# nixie_tester.net
KiCad netlist of a schematic drawn in EAGLE
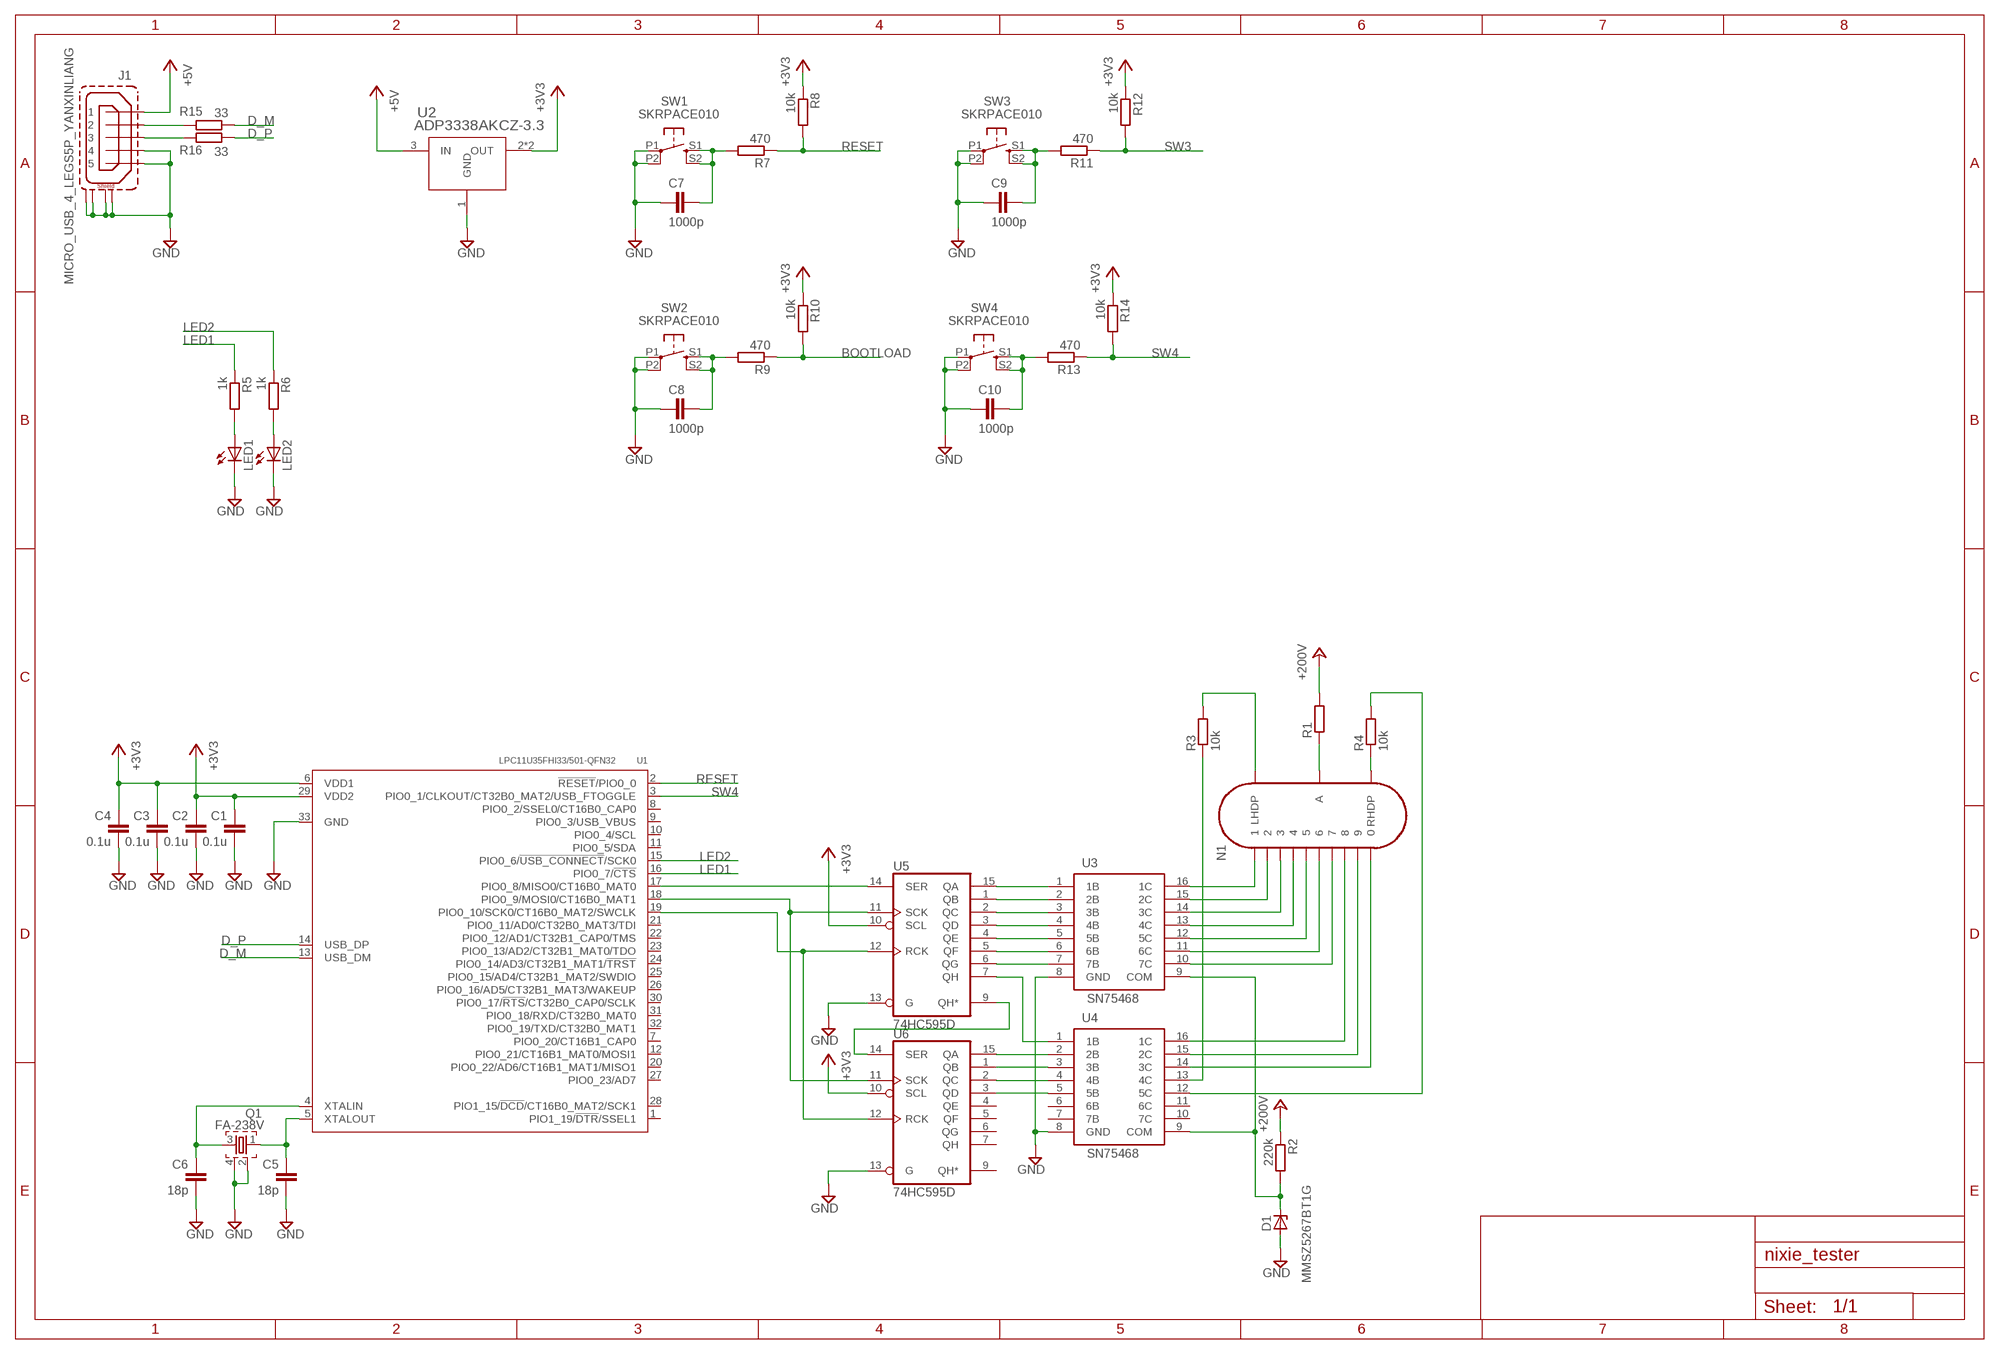
[diagram p0: schematic, sheet 1]

(export (version "E")
  (design (tool "Eeschema 10.0.6"))
  (components
    (comp (ref "C1")
      (value "0.1u")
      (footprint "eagle-import:C0603")
      (libsource (lib "eagle-import") (part "C-EUC0603"))
    )
    (comp (ref "C2")
      (value "0.1u")
      (footprint "eagle-import:C0603")
      (libsource (lib "eagle-import") (part "C-EUC0603"))
    )
    (comp (ref "C3")
      (value "0.1u")
      (footprint "eagle-import:C0603")
      (libsource (lib "eagle-import") (part "C-EUC0603"))
    )
    (comp (ref "C4")
      (value "0.1u")
      (footprint "eagle-import:C0603")
      (libsource (lib "eagle-import") (part "C-EUC0603"))
    )
    (comp (ref "C5")
      (value "18p")
      (footprint "eagle-import:C0603")
      (libsource (lib "eagle-import") (part "C-EUC0603"))
    )
    (comp (ref "C6")
      (value "18p")
      (footprint "eagle-import:C0603")
      (libsource (lib "eagle-import") (part "C-EUC0603"))
    )
    (comp (ref "C7")
      (value "1000p")
      (footprint "eagle-import:C0603")
      (libsource (lib "eagle-import") (part "C-EUC0603"))
    )
    (comp (ref "C8")
      (value "1000p")
      (footprint "eagle-import:C0603")
      (libsource (lib "eagle-import") (part "C-EUC0603"))
    )
    (comp (ref "C9")
      (value "1000p")
      (footprint "eagle-import:C0603")
      (libsource (lib "eagle-import") (part "C-EUC0603"))
    )
    (comp (ref "C10")
      (value "1000p")
      (footprint "eagle-import:C0603")
      (libsource (lib "eagle-import") (part "C-EUC0603"))
    )
    (comp (ref "D1")
      (value "MMSZ5267BT1G")
      (footprint "eagle-import:SOD123")
      (libsource (lib "eagle-import") (part "MMSZ5267BT1G"))
    )
    (comp (ref "J1")
      (value "MICRO_USB_4_LEGS5P_YANXINLIANG")
      (footprint "eagle-import:MICRO_USB_4_LEGS5P_YANXINLIANG")
      (libsource (lib "eagle-import") (part "MICRO_USB_4_LEGS5P_YANXINLIANG"))
    )
    (comp (ref "LED1")
      (value "LEDCHIPLED_0603")
      (footprint "eagle-import:CHIPLED_0603")
      (libsource (lib "eagle-import") (part "LEDCHIPLED_0603"))
    )
    (comp (ref "LED2")
      (value "LEDCHIPLED_0603")
      (footprint "eagle-import:CHIPLED_0603")
      (libsource (lib "eagle-import") (part "LEDCHIPLED_0603"))
    )
    (comp (ref "N1")
      (value "IN-14")
      (footprint "eagle-import:IN-14")
      (libsource (lib "eagle-import") (part "IN-14"))
    )
    (comp (ref "Q1")
      (value "FA-238V")
      (footprint "eagle-import:FA238-V")
      (libsource (lib "eagle-import") (part "FA-238V"))
    )
    (comp (ref "R1")
      (value "R-EU_R1206")
      (footprint "eagle-import:R1206")
      (libsource (lib "eagle-import") (part "R-EU_R1206"))
    )
    (comp (ref "R2")
      (value "220k")
      (footprint "eagle-import:R0603")
      (libsource (lib "eagle-import") (part "R-EU_R0603"))
    )
    (comp (ref "R3")
      (value "10k")
      (footprint "eagle-import:R0603")
      (libsource (lib "eagle-import") (part "R-EU_R0603"))
    )
    (comp (ref "R4")
      (value "10k")
      (footprint "eagle-import:R0603")
      (libsource (lib "eagle-import") (part "R-EU_R0603"))
    )
    (comp (ref "R5")
      (value "1k")
      (footprint "eagle-import:R0603")
      (libsource (lib "eagle-import") (part "R-EU_R0603"))
    )
    (comp (ref "R6")
      (value "1k")
      (footprint "eagle-import:R0603")
      (libsource (lib "eagle-import") (part "R-EU_R0603"))
    )
    (comp (ref "R7")
      (value "470")
      (footprint "eagle-import:R0603")
      (libsource (lib "eagle-import") (part "R-EU_R0603"))
    )
    (comp (ref "R8")
      (value "10k")
      (footprint "eagle-import:R0603")
      (libsource (lib "eagle-import") (part "R-EU_R0603"))
    )
    (comp (ref "R9")
      (value "470")
      (footprint "eagle-import:R0603")
      (libsource (lib "eagle-import") (part "R-EU_R0603"))
    )
    (comp (ref "R10")
      (value "10k")
      (footprint "eagle-import:R0603")
      (libsource (lib "eagle-import") (part "R-EU_R0603"))
    )
    (comp (ref "R11")
      (value "470")
      (footprint "eagle-import:R0603")
      (libsource (lib "eagle-import") (part "R-EU_R0603"))
    )
    (comp (ref "R12")
      (value "10k")
      (footprint "eagle-import:R0603")
      (libsource (lib "eagle-import") (part "R-EU_R0603"))
    )
    (comp (ref "R13")
      (value "470")
      (footprint "eagle-import:R0603")
      (libsource (lib "eagle-import") (part "R-EU_R0603"))
    )
    (comp (ref "R14")
      (value "10k")
      (footprint "eagle-import:R0603")
      (libsource (lib "eagle-import") (part "R-EU_R0603"))
    )
    (comp (ref "R15")
      (value "33")
      (footprint "eagle-import:R0603")
      (libsource (lib "eagle-import") (part "R-EU_R0603"))
    )
    (comp (ref "R16")
      (value "33")
      (footprint "eagle-import:R0603")
      (libsource (lib "eagle-import") (part "R-EU_R0603"))
    )
    (comp (ref "SW1")
      (value "SKRPACE010")
      (footprint "eagle-import:SKRPACE010")
      (libsource (lib "eagle-import") (part "SKRPACE010"))
    )
    (comp (ref "SW2")
      (value "SKRPACE010")
      (footprint "eagle-import:SKRPACE010")
      (libsource (lib "eagle-import") (part "SKRPACE010"))
    )
    (comp (ref "SW3")
      (value "SKRPACE010")
      (footprint "eagle-import:SKRPACE010")
      (libsource (lib "eagle-import") (part "SKRPACE010"))
    )
    (comp (ref "SW4")
      (value "SKRPACE010")
      (footprint "eagle-import:SKRPACE010")
      (libsource (lib "eagle-import") (part "SKRPACE010"))
    )
    (comp (ref "U1")
      (value "LPC11U35FHI33/501-QFN32")
      (footprint "eagle-import:QFN32G-0.5-5X5MM")
      (fields (field (name "MPN") "LPC11U35FHI33/501"))
      (libsource (lib "eagle-import") (part "MCU-LPC11U35FHI33/501(QFN32)"))
    )
    (comp (ref "U2")
      (value "ADP3338AKCZ-3.3")
      (footprint "eagle-import:SOT233")
      (libsource (lib "eagle-import") (part "ADP3338AKCZ-3.3"))
    )
    (comp (ref "U3")
      (value "SN75468")
      (footprint "eagle-import:R-PDSO-G16")
      (libsource (lib "eagle-import") (part "SN75468"))
    )
    (comp (ref "U4")
      (value "SN75468")
      (footprint "eagle-import:R-PDSO-G16")
      (libsource (lib "eagle-import") (part "SN75468"))
    )
    (comp (ref "U5")
      (value "74HC595D")
      (footprint "eagle-import:SO16")
      (libsource (lib "eagle-import") (part "74595DHC"))
    )
    (comp (ref "U6")
      (value "74HC595D")
      (footprint "eagle-import:SO16")
      (libsource (lib "eagle-import") (part "74595DHC"))
    )
  )
  (nets
    (net (code "1") (name "+3V3") (class "Default")
      (node (ref "C1") (pin "1") (pinfunction "1_1") (pintype "passive"))
      (node (ref "C2") (pin "1") (pinfunction "1_1") (pintype "passive"))
      (node (ref "C3") (pin "1") (pinfunction "1_1") (pintype "passive"))
      (node (ref "C4") (pin "1") (pinfunction "1_1") (pintype "passive"))
      (node (ref "R10") (pin "1") (pinfunction "1_1") (pintype "passive"))
      (node (ref "R12") (pin "1") (pinfunction "1_1") (pintype "passive"))
      (node (ref "R14") (pin "1") (pinfunction "1_1") (pintype "passive"))
      (node (ref "R8") (pin "1") (pinfunction "1_1") (pintype "passive"))
      (node (ref "U1") (pin "29") (pinfunction "VDD2_29") (pintype "bidirectional"))
      (node (ref "U1") (pin "6") (pinfunction "VDD1_6") (pintype "bidirectional"))
      (node (ref "U2") (pin "2") (pinfunction "OUT_2") (pintype "passive"))
      (node (ref "U2") (pin "4") (pinfunction "OUT_4") (pintype "passive"))
      (node (ref "U5") (pin "10") (pinfunction "SCL_10") (pintype "input"))
      (node (ref "U6") (pin "10") (pinfunction "SCL_10") (pintype "input"))
    )
    (net (code "2") (name "+5V") (class "Default")
      (node (ref "J1") (pin "1") (pinfunction "1_1") (pintype "input"))
      (node (ref "U2") (pin "3") (pinfunction "IN_3") (pintype "passive"))
    )
    (net (code "3") (name "+200V") (class "Default")
      (node (ref "R1") (pin "2") (pinfunction "2_2") (pintype "passive"))
      (node (ref "R2") (pin "1") (pinfunction "1_1") (pintype "passive"))
    )
    (net (code "4") (name "/BOOTLOAD") (class "Default")
      (node (ref "R10") (pin "2") (pinfunction "2_2") (pintype "passive"))
      (node (ref "R9") (pin "1") (pinfunction "1_1") (pintype "passive"))
    )
    (net (code "5") (name "/D_M") (class "Default")
      (node (ref "R15") (pin "1") (pinfunction "1_1") (pintype "passive"))
      (node (ref "U1") (pin "13") (pinfunction "USB_DM_13") (pintype "bidirectional"))
    )
    (net (code "6") (name "/D_P") (class "Default")
      (node (ref "R16") (pin "1") (pinfunction "1_1") (pintype "passive"))
      (node (ref "U1") (pin "14") (pinfunction "USB_DP_14") (pintype "bidirectional"))
    )
    (net (code "7") (name "/LED1") (class "Default")
      (node (ref "R5") (pin "1") (pinfunction "1_1") (pintype "passive"))
      (node (ref "U1") (pin "16") (pinfunction "PIO0_7/~{CTS}_16") (pintype "bidirectional"))
    )
    (net (code "8") (name "/LED2") (class "Default")
      (node (ref "R6") (pin "1") (pinfunction "1_1") (pintype "passive"))
      (node (ref "U1") (pin "15") (pinfunction "PIO0_6/~{USB_CONNECT}/SCK0_15") (pintype "bidirectional"))
    )
    (net (code "9") (name "/RESET") (class "Default")
      (node (ref "R7") (pin "1") (pinfunction "1_1") (pintype "passive"))
      (node (ref "R8") (pin "2") (pinfunction "2_2") (pintype "passive"))
      (node (ref "U1") (pin "2") (pinfunction "~{RESET}/PIO0_0_2") (pintype "bidirectional"))
    )
    (net (code "10") (name "/SW3") (class "Default")
      (node (ref "R11") (pin "1") (pinfunction "1_1") (pintype "passive"))
      (node (ref "R12") (pin "2") (pinfunction "2_2") (pintype "passive"))
    )
    (net (code "11") (name "/SW4") (class "Default")
      (node (ref "R13") (pin "1") (pinfunction "1_1") (pintype "passive"))
      (node (ref "R14") (pin "2") (pinfunction "2_2") (pintype "passive"))
      (node (ref "U1") (pin "3") (pinfunction "PIO0_1/CLKOUT/CT32B0_MAT2/USB_FTOGGLE_3") (pintype "bidirectional"))
    )
    (net (code "12") (name "GND") (class "Default")
      (node (ref "C1") (pin "2") (pinfunction "2_2") (pintype "passive"))
      (node (ref "C10") (pin "1") (pinfunction "1_1") (pintype "passive"))
      (node (ref "C2") (pin "2") (pinfunction "2_2") (pintype "passive"))
      (node (ref "C3") (pin "2") (pinfunction "2_2") (pintype "passive"))
      (node (ref "C4") (pin "2") (pinfunction "2_2") (pintype "passive"))
      (node (ref "C5") (pin "2") (pinfunction "2_2") (pintype "passive"))
      (node (ref "C6") (pin "2") (pinfunction "2_2") (pintype "passive"))
      (node (ref "C7") (pin "1") (pinfunction "1_1") (pintype "passive"))
      (node (ref "C8") (pin "1") (pinfunction "1_1") (pintype "passive"))
      (node (ref "C9") (pin "1") (pinfunction "1_1") (pintype "passive"))
      (node (ref "D1") (pin "A") (pinfunction "A_A") (pintype "passive"))
      (node (ref "J1") (pin "4") (pinfunction "4_4") (pintype "input"))
      (node (ref "J1") (pin "5") (pinfunction "5_5") (pintype "input"))
      (node (ref "J1") (pin "S3") (pinfunction "S3_S3") (pintype "passive"))
      (node (ref "J1") (pin "S4") (pinfunction "S4_S4") (pintype "passive"))
      (node (ref "J1") (pin "S5") (pinfunction "S5_S5") (pintype "passive"))
      (node (ref "J1") (pin "S6") (pinfunction "S6_S6") (pintype "passive"))
      (node (ref "LED1") (pin "C") (pinfunction "C_C") (pintype "passive"))
      (node (ref "LED2") (pin "C") (pinfunction "C_C") (pintype "passive"))
      (node (ref "Q1") (pin "2") (pinfunction "2_2") (pintype "passive"))
      (node (ref "Q1") (pin "4") (pinfunction "4_4") (pintype "passive"))
      (node (ref "SW1") (pin "P1") (pinfunction "P_P1") (pintype "passive"))
      (node (ref "SW1") (pin "P2") (pinfunction "P1_P2") (pintype "passive"))
      (node (ref "SW2") (pin "P1") (pinfunction "P_P1") (pintype "passive"))
      (node (ref "SW2") (pin "P2") (pinfunction "P1_P2") (pintype "passive"))
      (node (ref "SW3") (pin "P1") (pinfunction "P_P1") (pintype "passive"))
      (node (ref "SW3") (pin "P2") (pinfunction "P1_P2") (pintype "passive"))
      (node (ref "SW4") (pin "P1") (pinfunction "P_P1") (pintype "passive"))
      (node (ref "SW4") (pin "P2") (pinfunction "P1_P2") (pintype "passive"))
      (node (ref "U1") (pin "33") (pinfunction "GND_33") (pintype "bidirectional"))
      (node (ref "U2") (pin "1") (pinfunction "GND_1") (pintype "passive"))
      (node (ref "U3") (pin "8") (pinfunction "GND_8") (pintype "bidirectional"))
      (node (ref "U4") (pin "8") (pinfunction "GND_8") (pintype "bidirectional"))
      (node (ref "U5") (pin "13") (pinfunction "G_13") (pintype "input"))
      (node (ref "U6") (pin "13") (pinfunction "G_13") (pintype "input"))
    )
    (net (code "13") (name "Net-(D1-C)") (class "Default")
      (node (ref "D1") (pin "K") (pinfunction "C_K") (pintype "passive"))
      (node (ref "R2") (pin "2") (pinfunction "2_2") (pintype "passive"))
      (node (ref "U3") (pin "9") (pinfunction "COM_9") (pintype "bidirectional"))
      (node (ref "U4") (pin "9") (pinfunction "COM_9") (pintype "bidirectional"))
    )
    (net (code "14") (name "Net-(J1-Pad2)") (class "Default")
      (node (ref "J1") (pin "2") (pinfunction "2_2") (pintype "input"))
      (node (ref "R15") (pin "2") (pinfunction "2_2") (pintype "passive"))
    )
    (net (code "15") (name "Net-(J1-Pad3)") (class "Default")
      (node (ref "J1") (pin "3") (pinfunction "3_3") (pintype "input"))
      (node (ref "R16") (pin "2") (pinfunction "2_2") (pintype "passive"))
    )
    (net (code "16") (name "Net-(LED1-PadA)") (class "Default")
      (node (ref "LED1") (pin "A") (pinfunction "A_A") (pintype "passive"))
      (node (ref "R5") (pin "2") (pinfunction "2_2") (pintype "passive"))
    )
    (net (code "17") (name "Net-(LED2-PadA)") (class "Default")
      (node (ref "LED2") (pin "A") (pinfunction "A_A") (pintype "passive"))
      (node (ref "R6") (pin "2") (pinfunction "2_2") (pintype "passive"))
    )
    (net (code "18") (name "Net-(N1-PadA)") (class "Default")
      (node (ref "N1") (pin "A") (pinfunction "A_A") (pintype "bidirectional"))
      (node (ref "R1") (pin "1") (pinfunction "1_1") (pintype "passive"))
    )
    (net (code "19") (name "Net-(N1-PadLHDP)") (class "Default")
      (node (ref "N1") (pin "LHDP") (pinfunction "LHDP_LHDP") (pintype "bidirectional"))
      (node (ref "R3") (pin "2") (pinfunction "2_2") (pintype "passive"))
    )
    (net (code "20") (name "Net-(N1-PadRHDP)") (class "Default")
      (node (ref "N1") (pin "RHDP") (pinfunction "RHDP_RHDP") (pintype "bidirectional"))
      (node (ref "R4") (pin "1") (pinfunction "1_1") (pintype "passive"))
    )
    (net (code "21") (name "Net-(SW1-S)") (class "Default")
      (node (ref "C7") (pin "2") (pinfunction "2_2") (pintype "passive"))
      (node (ref "R7") (pin "2") (pinfunction "2_2") (pintype "passive"))
      (node (ref "SW1") (pin "S1") (pinfunction "S_S1") (pintype "passive"))
      (node (ref "SW1") (pin "S2") (pinfunction "S1_S2") (pintype "passive"))
    )
    (net (code "22") (name "Net-(SW2-S)") (class "Default")
      (node (ref "C8") (pin "2") (pinfunction "2_2") (pintype "passive"))
      (node (ref "R9") (pin "2") (pinfunction "2_2") (pintype "passive"))
      (node (ref "SW2") (pin "S1") (pinfunction "S_S1") (pintype "passive"))
      (node (ref "SW2") (pin "S2") (pinfunction "S1_S2") (pintype "passive"))
    )
    (net (code "23") (name "Net-(SW3-S)") (class "Default")
      (node (ref "C9") (pin "2") (pinfunction "2_2") (pintype "passive"))
      (node (ref "R11") (pin "2") (pinfunction "2_2") (pintype "passive"))
      (node (ref "SW3") (pin "S1") (pinfunction "S_S1") (pintype "passive"))
      (node (ref "SW3") (pin "S2") (pinfunction "S1_S2") (pintype "passive"))
    )
    (net (code "24") (name "Net-(SW4-S)") (class "Default")
      (node (ref "C10") (pin "2") (pinfunction "2_2") (pintype "passive"))
      (node (ref "R13") (pin "2") (pinfunction "2_2") (pintype "passive"))
      (node (ref "SW4") (pin "S1") (pinfunction "S_S1") (pintype "passive"))
      (node (ref "SW4") (pin "S2") (pinfunction "S1_S2") (pintype "passive"))
    )
    (net (code "25") (name "Net-(U1-PIO0_8{slash}MISO0{slash}CT16B0_MAT0)") (class "Default")
      (node (ref "U1") (pin "17") (pinfunction "PIO0_8/MISO0/CT16B0_MAT0_17") (pintype "bidirectional"))
      (node (ref "U5") (pin "14") (pinfunction "SER_14") (pintype "input"))
    )
    (net (code "26") (name "Net-(U1-PIO0_9{slash}MOSI0{slash}CT16B0_MAT1)") (class "Default")
      (node (ref "U1") (pin "18") (pinfunction "PIO0_9/MOSI0/CT16B0_MAT1_18") (pintype "bidirectional"))
      (node (ref "U5") (pin "11") (pinfunction "SCK_11") (pintype "input"))
      (node (ref "U6") (pin "11") (pinfunction "SCK_11") (pintype "input"))
    )
    (net (code "27") (name "Net-(U1-PIO0_10{slash}SCK0{slash}CT16B0_MAT2{slash}SWCLK)") (class "Default")
      (node (ref "U1") (pin "19") (pinfunction "PIO0_10/SCK0/CT16B0_MAT2/SWCLK_19") (pintype "bidirectional"))
      (node (ref "U5") (pin "12") (pinfunction "RCK_12") (pintype "input"))
      (node (ref "U6") (pin "12") (pinfunction "RCK_12") (pintype "input"))
    )
    (net (code "28") (name "Net-(U1-XTALIN)") (class "Default")
      (node (ref "C6") (pin "1") (pinfunction "1_1") (pintype "passive"))
      (node (ref "Q1") (pin "3") (pinfunction "3_3") (pintype "passive"))
      (node (ref "U1") (pin "4") (pinfunction "XTALIN_4") (pintype "bidirectional"))
    )
    (net (code "29") (name "Net-(U1-XTALOUT)") (class "Default")
      (node (ref "C5") (pin "1") (pinfunction "1_1") (pintype "passive"))
      (node (ref "Q1") (pin "1") (pinfunction "1_1") (pintype "passive"))
      (node (ref "U1") (pin "5") (pinfunction "XTALOUT_5") (pintype "bidirectional"))
    )
    (net (code "30") (name "Net-(U3-1B)") (class "Default")
      (node (ref "U3") (pin "1") (pinfunction "1B_1") (pintype "bidirectional"))
      (node (ref "U5") (pin "15") (pinfunction "QA_15") (pintype "tri_state"))
    )
    (net (code "31") (name "Net-(U3-1C)") (class "Default")
      (node (ref "N1") (pin "1") (pinfunction "1_1") (pintype "bidirectional"))
      (node (ref "U3") (pin "16") (pinfunction "1C_16") (pintype "bidirectional"))
    )
    (net (code "32") (name "Net-(U3-2B)") (class "Default")
      (node (ref "U3") (pin "2") (pinfunction "2B_2") (pintype "bidirectional"))
      (node (ref "U5") (pin "1") (pinfunction "QB_1") (pintype "tri_state"))
    )
    (net (code "33") (name "Net-(U3-2C)") (class "Default")
      (node (ref "N1") (pin "2") (pinfunction "2_2") (pintype "bidirectional"))
      (node (ref "U3") (pin "15") (pinfunction "2C_15") (pintype "bidirectional"))
    )
    (net (code "34") (name "Net-(U3-3B)") (class "Default")
      (node (ref "U3") (pin "3") (pinfunction "3B_3") (pintype "bidirectional"))
      (node (ref "U5") (pin "2") (pinfunction "QC_2") (pintype "tri_state"))
    )
    (net (code "35") (name "Net-(U3-3C)") (class "Default")
      (node (ref "N1") (pin "3") (pinfunction "3_3") (pintype "bidirectional"))
      (node (ref "U3") (pin "14") (pinfunction "3C_14") (pintype "bidirectional"))
    )
    (net (code "36") (name "Net-(U3-4B)") (class "Default")
      (node (ref "U3") (pin "4") (pinfunction "4B_4") (pintype "bidirectional"))
      (node (ref "U5") (pin "3") (pinfunction "QD_3") (pintype "tri_state"))
    )
    (net (code "37") (name "Net-(U3-4C)") (class "Default")
      (node (ref "N1") (pin "4") (pinfunction "4_4") (pintype "bidirectional"))
      (node (ref "U3") (pin "13") (pinfunction "4C_13") (pintype "bidirectional"))
    )
    (net (code "38") (name "Net-(U3-5B)") (class "Default")
      (node (ref "U3") (pin "5") (pinfunction "5B_5") (pintype "bidirectional"))
      (node (ref "U5") (pin "4") (pinfunction "QE_4") (pintype "tri_state"))
    )
    (net (code "39") (name "Net-(U3-5C)") (class "Default")
      (node (ref "N1") (pin "5") (pinfunction "5_5") (pintype "bidirectional"))
      (node (ref "U3") (pin "12") (pinfunction "5C_12") (pintype "bidirectional"))
    )
    (net (code "40") (name "Net-(U3-6B)") (class "Default")
      (node (ref "U3") (pin "6") (pinfunction "6B_6") (pintype "bidirectional"))
      (node (ref "U5") (pin "5") (pinfunction "QF_5") (pintype "tri_state"))
    )
    (net (code "41") (name "Net-(U3-6C)") (class "Default")
      (node (ref "N1") (pin "6") (pinfunction "6_6") (pintype "bidirectional"))
      (node (ref "U3") (pin "11") (pinfunction "6C_11") (pintype "bidirectional"))
    )
    (net (code "42") (name "Net-(U3-7B)") (class "Default")
      (node (ref "U3") (pin "7") (pinfunction "7B_7") (pintype "bidirectional"))
      (node (ref "U5") (pin "6") (pinfunction "QG_6") (pintype "tri_state"))
    )
    (net (code "43") (name "Net-(U3-7C)") (class "Default")
      (node (ref "N1") (pin "7") (pinfunction "7_7") (pintype "bidirectional"))
      (node (ref "U3") (pin "10") (pinfunction "7C_10") (pintype "bidirectional"))
    )
    (net (code "44") (name "Net-(U4-1B)") (class "Default")
      (node (ref "U4") (pin "1") (pinfunction "1B_1") (pintype "bidirectional"))
      (node (ref "U5") (pin "7") (pinfunction "QH_7") (pintype "tri_state"))
    )
    (net (code "45") (name "Net-(U4-1C)") (class "Default")
      (node (ref "N1") (pin "8") (pinfunction "8_8") (pintype "bidirectional"))
      (node (ref "U4") (pin "16") (pinfunction "1C_16") (pintype "bidirectional"))
    )
    (net (code "46") (name "Net-(U4-2B)") (class "Default")
      (node (ref "U4") (pin "2") (pinfunction "2B_2") (pintype "bidirectional"))
      (node (ref "U6") (pin "15") (pinfunction "QA_15") (pintype "tri_state"))
    )
    (net (code "47") (name "Net-(U4-2C)") (class "Default")
      (node (ref "N1") (pin "9") (pinfunction "9_9") (pintype "bidirectional"))
      (node (ref "U4") (pin "15") (pinfunction "2C_15") (pintype "bidirectional"))
    )
    (net (code "48") (name "Net-(U4-3B)") (class "Default")
      (node (ref "U4") (pin "3") (pinfunction "3B_3") (pintype "bidirectional"))
      (node (ref "U6") (pin "1") (pinfunction "QB_1") (pintype "tri_state"))
    )
    (net (code "49") (name "Net-(U4-3C)") (class "Default")
      (node (ref "N1") (pin "0") (pinfunction "0_0") (pintype "bidirectional"))
      (node (ref "U4") (pin "14") (pinfunction "3C_14") (pintype "bidirectional"))
    )
    (net (code "50") (name "Net-(U4-4B)") (class "Default")
      (node (ref "U4") (pin "4") (pinfunction "4B_4") (pintype "bidirectional"))
      (node (ref "U6") (pin "2") (pinfunction "QC_2") (pintype "tri_state"))
    )
    (net (code "51") (name "Net-(U4-4C)") (class "Default")
      (node (ref "R3") (pin "1") (pinfunction "1_1") (pintype "passive"))
      (node (ref "U4") (pin "13") (pinfunction "4C_13") (pintype "bidirectional"))
    )
    (net (code "52") (name "Net-(U4-5B)") (class "Default")
      (node (ref "U4") (pin "5") (pinfunction "5B_5") (pintype "bidirectional"))
      (node (ref "U6") (pin "3") (pinfunction "QD_3") (pintype "tri_state"))
    )
    (net (code "53") (name "Net-(U4-5C)") (class "Default")
      (node (ref "R4") (pin "2") (pinfunction "2_2") (pintype "passive"))
      (node (ref "U4") (pin "12") (pinfunction "5C_12") (pintype "bidirectional"))
    )
    (net (code "54") (name "Net-(U5A-QH*)") (class "Default")
      (node (ref "U5") (pin "9") (pinfunction "QH*_9") (pintype "tri_state"))
      (node (ref "U6") (pin "14") (pinfunction "SER_14") (pintype "input"))
    )
    (net (code "55") (name "unconnected-(U1-PIO0_2{slash}SSEL0{slash}CT16B0_CAP0-Pad8)") (class "Default")
      (node (ref "U1") (pin "8") (pinfunction "PIO0_2/SSEL0/CT16B0_CAP0_8") (pintype "bidirectional"))
    )
    (net (code "56") (name "unconnected-(U1-PIO0_3{slash}USB_VBUS-Pad9)") (class "Default")
      (node (ref "U1") (pin "9") (pinfunction "PIO0_3/USB_VBUS_9") (pintype "bidirectional"))
    )
    (net (code "57") (name "unconnected-(U1-PIO0_4{slash}SCL-Pad10)") (class "Default")
      (node (ref "U1") (pin "10") (pinfunction "PIO0_4/SCL_10") (pintype "bidirectional"))
    )
    (net (code "58") (name "unconnected-(U1-PIO0_5{slash}SDA-Pad11)") (class "Default")
      (node (ref "U1") (pin "11") (pinfunction "PIO0_5/SDA_11") (pintype "bidirectional"))
    )
    (net (code "59") (name "unconnected-(U1-PIO0_11{slash}AD0{slash}CT32B0_MAT3{slash}TDI-Pad21)") (class "Default")
      (node (ref "U1") (pin "21") (pinfunction "PIO0_11/AD0/CT32B0_MAT3/TDI_21") (pintype "bidirectional"))
    )
    (net (code "60") (name "unconnected-(U1-PIO0_12{slash}AD1{slash}CT32B1_CAP0{slash}TMS-Pad22)") (class "Default")
      (node (ref "U1") (pin "22") (pinfunction "PIO0_12/AD1/CT32B1_CAP0/TMS_22") (pintype "bidirectional"))
    )
    (net (code "61") (name "unconnected-(U1-PIO0_13{slash}AD2{slash}CT32B1_MAT0{slash}TDO-Pad23)") (class "Default")
      (node (ref "U1") (pin "23") (pinfunction "PIO0_13/AD2/CT32B1_MAT0/TDO_23") (pintype "bidirectional"))
    )
    (net (code "62") (name "unconnected-(U1-PIO0_14{slash}AD3{slash}CT32B1_MAT1{slash}~{TRST}-Pad24)") (class "Default")
      (node (ref "U1") (pin "24") (pinfunction "PIO0_14/AD3/CT32B1_MAT1/~{TRST}_24") (pintype "bidirectional"))
    )
    (net (code "63") (name "unconnected-(U1-PIO0_15{slash}AD4{slash}CT32B1_MAT2{slash}SWDIO-Pad25)") (class "Default")
      (node (ref "U1") (pin "25") (pinfunction "PIO0_15/AD4/CT32B1_MAT2/SWDIO_25") (pintype "bidirectional"))
    )
    (net (code "64") (name "unconnected-(U1-PIO0_16{slash}AD5{slash}CT32B1_MAT3{slash}WAKEUP-Pad26)") (class "Default")
      (node (ref "U1") (pin "26") (pinfunction "PIO0_16/AD5/CT32B1_MAT3/WAKEUP_26") (pintype "bidirectional"))
    )
    (net (code "65") (name "unconnected-(U1-PIO0_17{slash}~{RTS}{slash}CT32B0_CAP0{slash}SCLK-Pad30)") (class "Default")
      (node (ref "U1") (pin "30") (pinfunction "PIO0_17/~{RTS}/CT32B0_CAP0/SCLK_30") (pintype "bidirectional"))
    )
    (net (code "66") (name "unconnected-(U1-PIO0_18{slash}RXD{slash}CT32B0_MAT0-Pad31)") (class "Default")
      (node (ref "U1") (pin "31") (pinfunction "PIO0_18/RXD/CT32B0_MAT0_31") (pintype "bidirectional"))
    )
    (net (code "67") (name "unconnected-(U1-PIO0_19{slash}TXD{slash}CT32B0_MAT1-Pad32)") (class "Default")
      (node (ref "U1") (pin "32") (pinfunction "PIO0_19/TXD/CT32B0_MAT1_32") (pintype "bidirectional"))
    )
    (net (code "68") (name "unconnected-(U1-PIO0_20{slash}CT16B1_CAP0-Pad7)") (class "Default")
      (node (ref "U1") (pin "7") (pinfunction "PIO0_20/CT16B1_CAP0_7") (pintype "bidirectional"))
    )
    (net (code "69") (name "unconnected-(U1-PIO0_21{slash}CT16B1_MAT0{slash}MOSI1-Pad12)") (class "Default")
      (node (ref "U1") (pin "12") (pinfunction "PIO0_21/CT16B1_MAT0/MOSI1_12") (pintype "bidirectional"))
    )
    (net (code "70") (name "unconnected-(U1-PIO0_22{slash}AD6{slash}CT16B1_MAT1{slash}MISO1-Pad20)") (class "Default")
      (node (ref "U1") (pin "20") (pinfunction "PIO0_22/AD6/CT16B1_MAT1/MISO1_20") (pintype "bidirectional"))
    )
    (net (code "71") (name "unconnected-(U1-PIO0_23{slash}AD7-Pad27)") (class "Default")
      (node (ref "U1") (pin "27") (pinfunction "PIO0_23/AD7_27") (pintype "bidirectional"))
    )
    (net (code "72") (name "unconnected-(U1-PIO1_15{slash}~{DCD}{slash}CT16B0_MAT2{slash}SCK1-Pad28)") (class "Default")
      (node (ref "U1") (pin "28") (pinfunction "PIO1_15/~{DCD}/CT16B0_MAT2/SCK1_28") (pintype "bidirectional"))
    )
    (net (code "73") (name "unconnected-(U1-PIO1_19{slash}~{DTR}{slash}SSEL1-Pad1)") (class "Default")
      (node (ref "U1") (pin "1") (pinfunction "PIO1_19/~{DTR}/SSEL1_1") (pintype "bidirectional"))
    )
    (net (code "74") (name "unconnected-(U4-6B-Pad6)") (class "Default")
      (node (ref "U4") (pin "6") (pinfunction "6B_6") (pintype "bidirectional"))
    )
    (net (code "75") (name "unconnected-(U4-6C-Pad11)") (class "Default")
      (node (ref "U4") (pin "11") (pinfunction "6C_11") (pintype "bidirectional"))
    )
    (net (code "76") (name "unconnected-(U4-7B-Pad7)") (class "Default")
      (node (ref "U4") (pin "7") (pinfunction "7B_7") (pintype "bidirectional"))
    )
    (net (code "77") (name "unconnected-(U4-7C-Pad10)") (class "Default")
      (node (ref "U4") (pin "10") (pinfunction "7C_10") (pintype "bidirectional"))
    )
    (net (code "78") (name "unconnected-(U6A-QE-Pad4)") (class "Default")
      (node (ref "U6") (pin "4") (pinfunction "QE_4") (pintype "tri_state"))
    )
    (net (code "79") (name "unconnected-(U6A-QF-Pad5)") (class "Default")
      (node (ref "U6") (pin "5") (pinfunction "QF_5") (pintype "tri_state"))
    )
    (net (code "80") (name "unconnected-(U6A-QG-Pad6)") (class "Default")
      (node (ref "U6") (pin "6") (pinfunction "QG_6") (pintype "tri_state"))
    )
    (net (code "81") (name "unconnected-(U6A-QH*-Pad9)") (class "Default")
      (node (ref "U6") (pin "9") (pinfunction "QH*_9") (pintype "tri_state"))
    )
    (net (code "82") (name "unconnected-(U6A-QH-Pad7)") (class "Default")
      (node (ref "U6") (pin "7") (pinfunction "QH_7") (pintype "tri_state"))
    )
  )
)
